# TF.net
KiCad netlist of a schematic drawn in Altium Designer
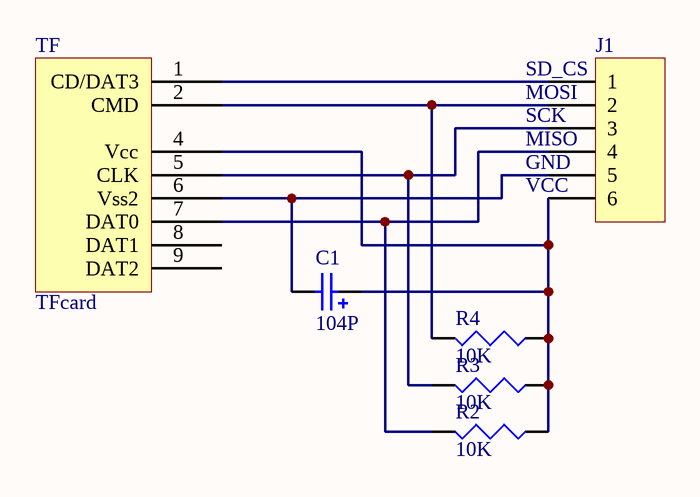
[diagram p0: TF.SchDoc]

(export (version "E")
  (design (tool "Eeschema 10.0.6"))
  (components
    (comp (ref "C1")
      (value "104P")
      (footprint "CC2012-0805")
      (description "Polarized Capacitor (Surface Mount)")
      (fields (field (name "Comment") "Cap Pol3") (field (name "PUBLISHER") "Altium Limited"))
      (libsource (lib "Miscellaneous Devices") (part "Cap Pol3"))
    )
    (comp (ref "J1")
      (value "Header 6")
      (footprint "HDR1X6")
      (description "Header, 6-Pin")
      (fields (field (name "PUBLISHER") "Altium Limited"))
      (libsource (lib "Miscellaneous Connectors") (part "Header 6"))
    )
    (comp (ref "R2")
      (value "10K")
      (footprint "R2012-0805")
      (description "Resistor")
      (fields (field (name "Comment") "Res3") (field (name "PUBLISHER") "Altium Limited"))
      (libsource (lib "Miscellaneous Devices") (part "Res3"))
    )
    (comp (ref "R3")
      (value "10K")
      (footprint "R2012-0805")
      (description "Resistor")
      (fields (field (name "Comment") "Res3") (field (name "PUBLISHER") "Altium Limited"))
      (libsource (lib "Miscellaneous Devices") (part "Res3"))
    )
    (comp (ref "R4")
      (value "10K")
      (footprint "R2012-0805")
      (description "Resistor")
      (fields (field (name "Comment") "Res3") (field (name "PUBLISHER") "Altium Limited"))
      (libsource (lib "Miscellaneous Devices") (part "Res3"))
    )
    (comp (ref "TF") (value "TFcard") (footprint "TF Card") (libsource (lib "TFCARD") (part "TFcard")))
  )
  (nets
    (net (code "1") (name "Net-(TF-CD{slash}DAT3)") (class "Default")
      (node (ref "J1") (pin "1") (pinfunction "1_1") (pintype "passive"))
      (node (ref "TF") (pin "1") (pinfunction "CD/DAT3_1") (pintype "passive"))
    )
    (net (code "2") (name "Net-(TF-CLK)") (class "Default")
      (node (ref "J1") (pin "3") (pinfunction "3_3") (pintype "passive"))
      (node (ref "R3") (pin "2") (pinfunction "2_2") (pintype "passive"))
      (node (ref "TF") (pin "5") (pinfunction "CLK_5") (pintype "passive"))
    )
    (net (code "3") (name "Net-(TF-CMD)") (class "Default")
      (node (ref "J1") (pin "2") (pinfunction "2_2") (pintype "passive"))
      (node (ref "R4") (pin "2") (pinfunction "2_2") (pintype "passive"))
      (node (ref "TF") (pin "2") (pinfunction "CMD_2") (pintype "passive"))
    )
    (net (code "4") (name "Net-(TF-DAT0)") (class "Default")
      (node (ref "J1") (pin "4") (pinfunction "4_4") (pintype "passive"))
      (node (ref "R2") (pin "2") (pinfunction "2_2") (pintype "passive"))
      (node (ref "TF") (pin "7") (pinfunction "DAT0_7") (pintype "passive"))
    )
    (net (code "5") (name "Net-(TF-Vcc)") (class "Default")
      (node (ref "C1") (pin "1") (pinfunction "1_1") (pintype "passive"))
      (node (ref "J1") (pin "6") (pinfunction "6_6") (pintype "passive"))
      (node (ref "R2") (pin "1") (pinfunction "1_1") (pintype "passive"))
      (node (ref "R3") (pin "1") (pinfunction "1_1") (pintype "passive"))
      (node (ref "R4") (pin "1") (pinfunction "1_1") (pintype "passive"))
      (node (ref "TF") (pin "4") (pinfunction "Vcc_4") (pintype "passive"))
    )
    (net (code "6") (name "Net-(TF-Vss2)") (class "Default")
      (node (ref "C1") (pin "2") (pinfunction "2_2") (pintype "passive"))
      (node (ref "J1") (pin "5") (pinfunction "5_5") (pintype "passive"))
      (node (ref "TF") (pin "6") (pinfunction "Vss2_6") (pintype "passive"))
    )
    (net (code "7") (name "unconnected-(TF-DAT1-Pad8)") (class "Default")
      (node (ref "TF") (pin "8") (pinfunction "DAT1_8") (pintype "passive"))
    )
    (net (code "8") (name "unconnected-(TF-DAT2-Pad9)") (class "Default")
      (node (ref "TF") (pin "9") (pinfunction "DAT2_9") (pintype "passive"))
    )
  )
)
